# E-11_SYS_PWR.net
KiCad netlist of a schematic drawn in Altium Designer
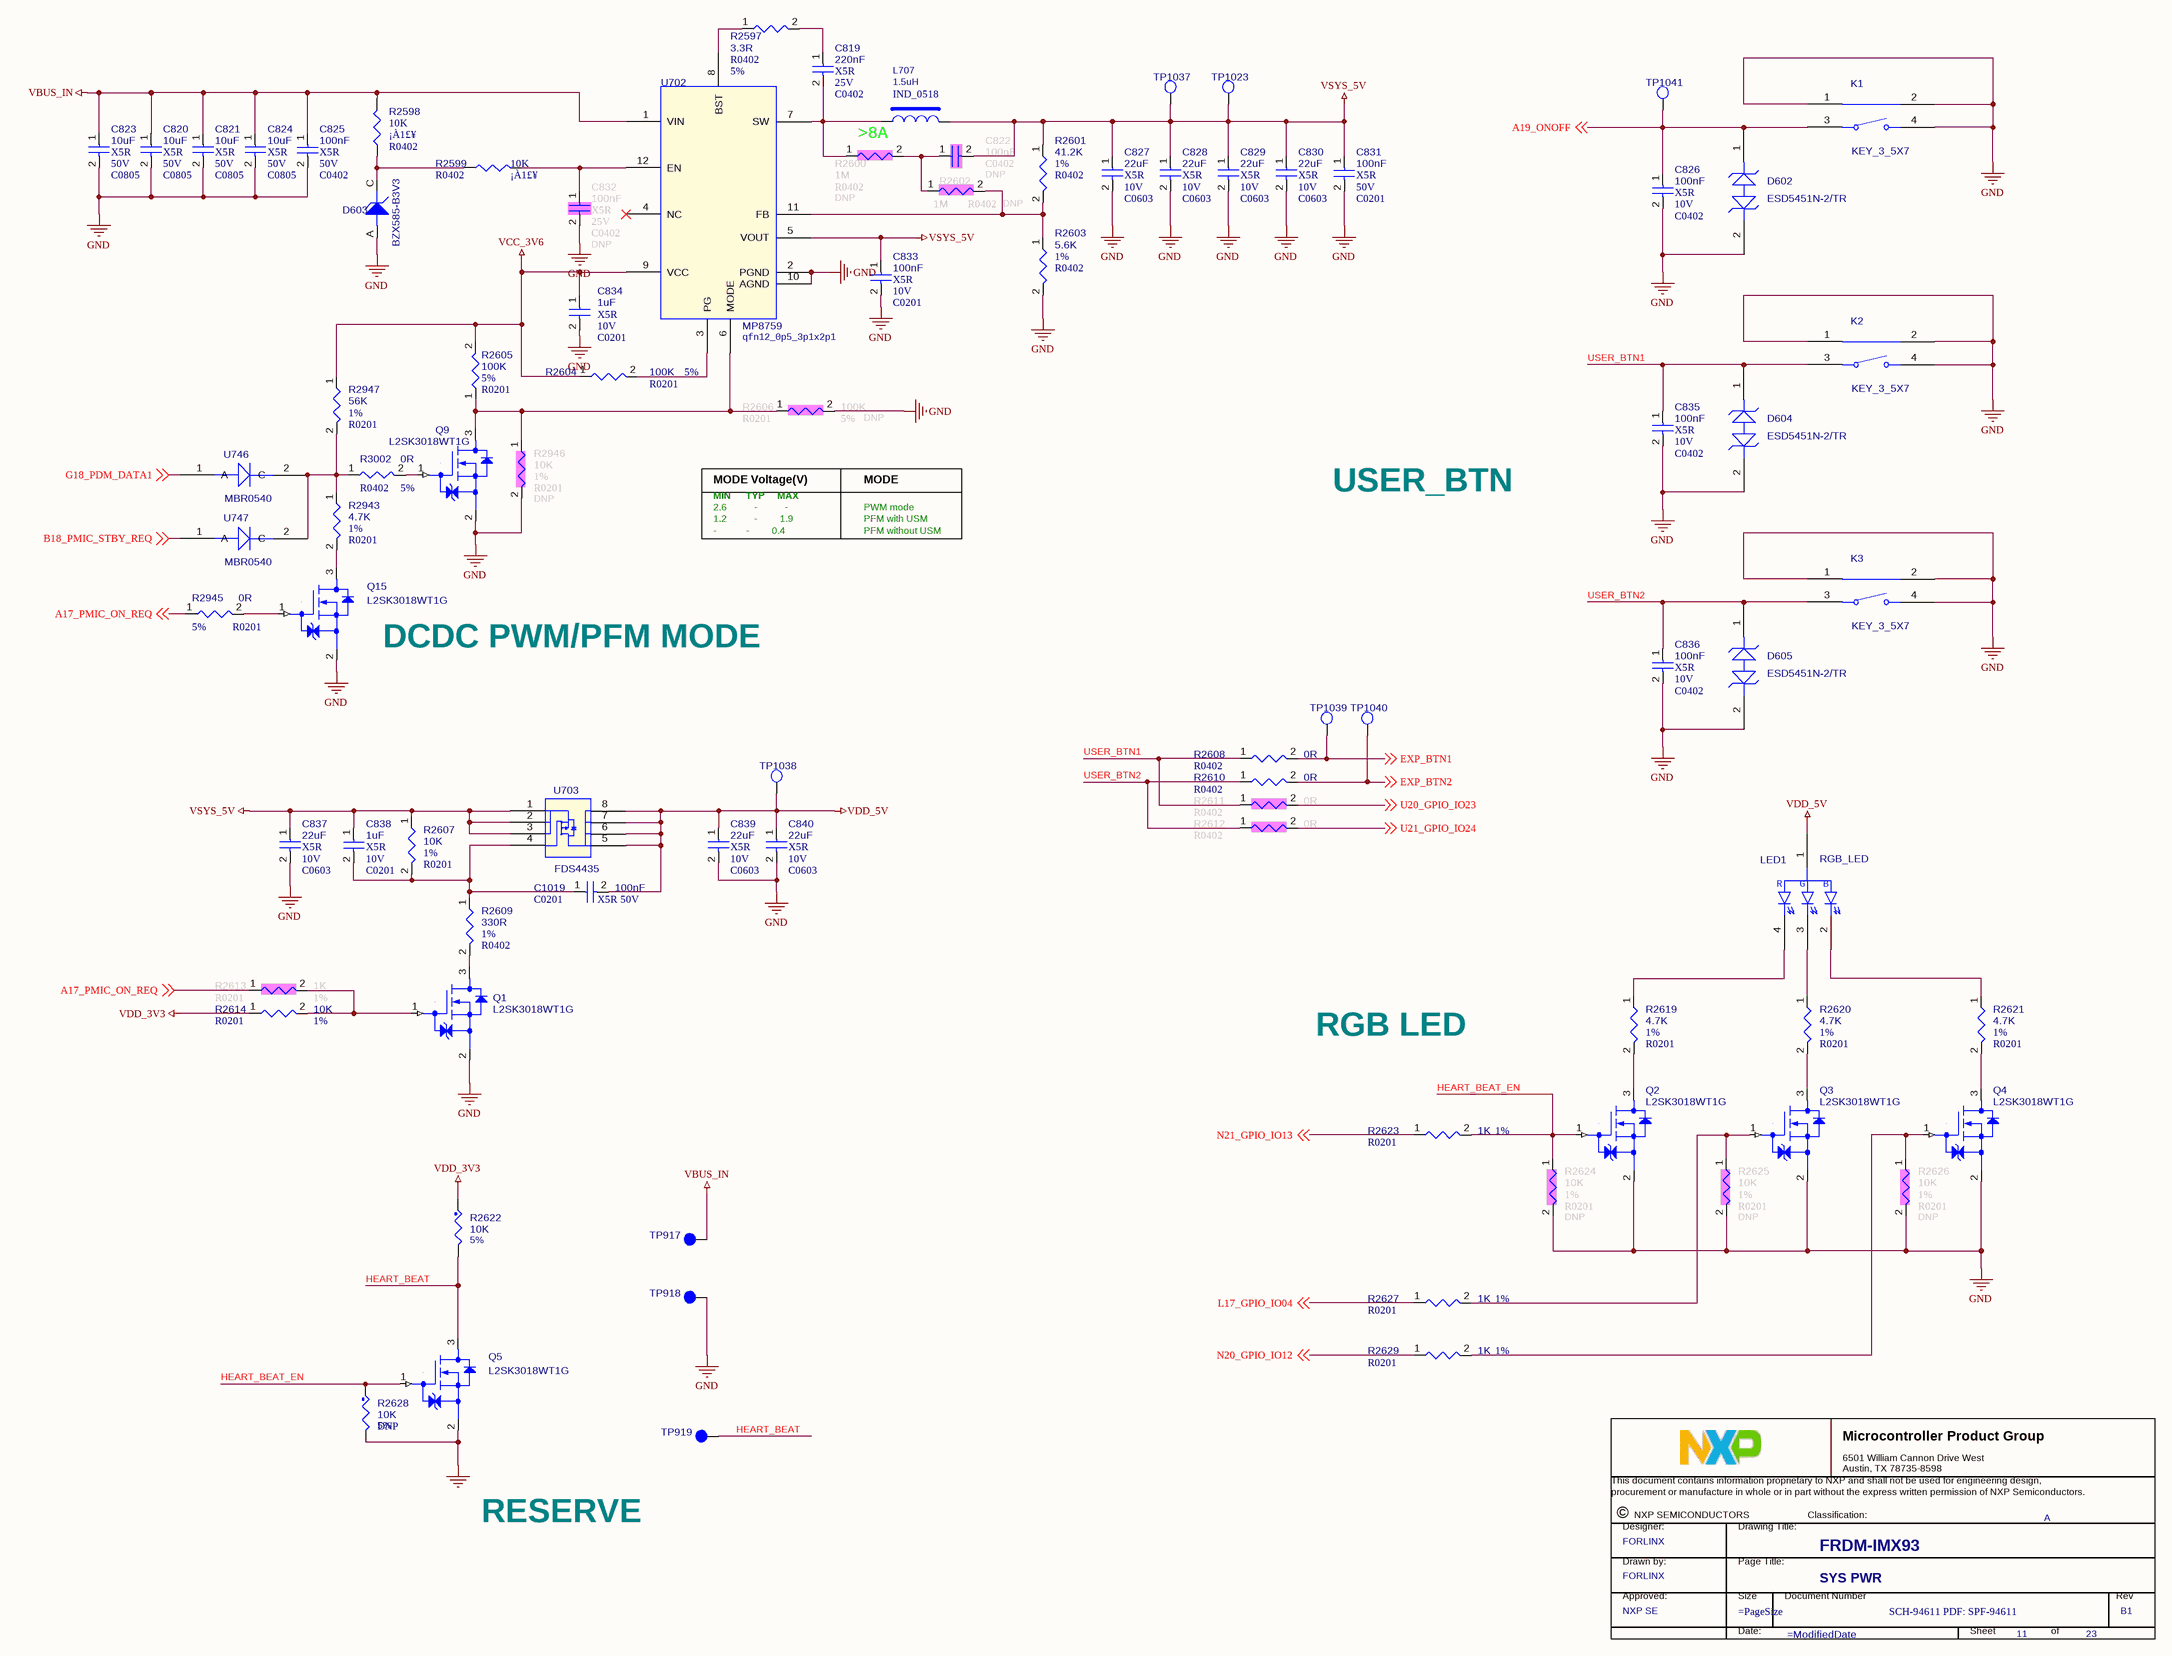
[diagram p0: E-11 SYS PWR.SchDoc]

(export (version "E")
  (design (tool "Eeschema 10.0.6"))
  (components
    (comp (ref "C819")
      (value "220nF")
      (footprint "C0402")
      (description "0402,220nF,25V,+/-10%,X5R")
      (fields
        (field (name "VOLTAGE") "25V")
        (field (name "PCB FOOTPRINT") "C0402")
        (field (name "DIELECTRIC") "X5R")
        (field (name "MANUFACTURER") "TDK")
        (field (name "TOLERANCE") "10%")
        (field (name "CREATED BY") "JJJ")
      )
      (libsource (lib "*") (part "CAP NP"))
    )
    (comp (ref "C820")
      (value "10uF")
      (footprint "C0805")
      (description "0805,10uF,50V,+/-10%,X5R")
      (fields
        (field (name "VOLTAGE") "50V")
        (field (name "PCB FOOTPRINT") "C0805")
        (field (name "DIELECTRIC") "X5R")
        (field (name "MANUFACTURER") "TDK")
        (field (name "TOLERANCE") "10%")
        (field (name "CREATED BY") "JJJ")
      )
      (libsource (lib "*") (part "CAP NP"))
    )
    (comp (ref "C821")
      (value "10uF")
      (footprint "C0805")
      (description "0805,10uF,50V,+/-10%,X5R")
      (fields
        (field (name "VOLTAGE") "50V")
        (field (name "PCB FOOTPRINT") "C0805")
        (field (name "DIELECTRIC") "X5R")
        (field (name "TOLERANCE") "10%")
        (field (name "MANUFACTURER") "TDK")
        (field (name "CREATED BY") "JJJ")
      )
      (libsource (lib "*") (part "CAP NP"))
    )
    (comp (ref "C822")
      (value "100nF")
      (footprint "C0402")
      (description "0402,100nF,50V,+/-10%,X5R")
      (fields
        (field (name "PCB FOOTPRINT") "C0402")
        (field (name "ASSY_OPT") "DNP")
        (field (name "CREATED BY") "JJJ")
      )
      (libsource (lib "*") (part "CAP NP"))
    )
    (comp (ref "C823")
      (value "10uF")
      (footprint "C0805")
      (description "0805,10uF,50V,+/-10%,X5R")
      (fields
        (field (name "VOLTAGE") "50V")
        (field (name "PCB FOOTPRINT") "C0805")
        (field (name "DIELECTRIC") "X5R")
        (field (name "MANUFACTURER") "TDK")
        (field (name "TOLERANCE") "10%")
        (field (name "CREATED BY") "JJJ")
      )
      (libsource (lib "*") (part "CAP NP"))
    )
    (comp (ref "C824")
      (value "10uF")
      (footprint "C0805")
      (description "0805,10uF,50V,+/-10%,X5R")
      (fields
        (field (name "VOLTAGE") "50V")
        (field (name "PCB FOOTPRINT") "C0805")
        (field (name "DIELECTRIC") "X5R")
        (field (name "TOLERANCE") "10%")
        (field (name "MANUFACTURER") "TDK")
        (field (name "CREATED BY") "JJJ")
      )
      (libsource (lib "*") (part "CAP NP"))
    )
    (comp (ref "C825")
      (value "100nF")
      (footprint "C0402")
      (description "0402,100nF,50V,+/-10%,X5R")
      (fields
        (field (name "VOLTAGE") "50V")
        (field (name "PCB FOOTPRINT") "C0402")
        (field (name "DIELECTRIC") "X5R")
        (field (name "TOLERANCE") "10%")
        (field (name "MANUFACTURER") "TDK")
        (field (name "CREATED BY") "JJJ")
      )
      (libsource (lib "*") (part "CAP NP"))
    )
    (comp (ref "C826")
      (value "100nF")
      (footprint "C0402")
      (description "0402,100nF,50V,+/-10%,X5R")
      (fields
        (field (name "VOLTAGE") "10V")
        (field (name "PCB FOOTPRINT") "C0402")
        (field (name "DIELECTRIC") "X5R")
        (field (name "TOLERANCE") "10%")
        (field (name "MANUFACTURER") "TDK")
        (field (name "CREATED BY") "JJJ")
      )
      (libsource (lib "*") (part "CAP NP"))
    )
    (comp (ref "C827")
      (value "22uF")
      (footprint "C0603")
      (description "0603,22uF,6.3V,+/-20%,X5R")
      (fields
        (field (name "VOLTAGE") "10V")
        (field (name "PCB FOOTPRINT") "C0603")
        (field (name "DIELECTRIC") "X5R")
        (field (name "MANUFACTURER") "TDK")
        (field (name "TOLERANCE") "10%")
        (field (name "CREATED BY") "JJJ")
      )
      (libsource (lib "*") (part "CAP NP"))
    )
    (comp (ref "C828")
      (value "22uF")
      (footprint "C0603")
      (description "0603,22uF,6.3V,+/-20%,X5R")
      (fields
        (field (name "VOLTAGE") "10V")
        (field (name "PCB FOOTPRINT") "C0603")
        (field (name "DIELECTRIC") "X5R")
        (field (name "MANUFACTURER") "TDK")
        (field (name "TOLERANCE") "10%")
        (field (name "CREATED BY") "JJJ")
      )
      (libsource (lib "*") (part "CAP NP"))
    )
    (comp (ref "C829")
      (value "22uF")
      (footprint "C0603")
      (description "0603,22uF,6.3V,+/-20%,X5R")
      (fields
        (field (name "VOLTAGE") "10V")
        (field (name "PCB FOOTPRINT") "C0603")
        (field (name "DIELECTRIC") "X5R")
        (field (name "TOLERANCE") "10%")
        (field (name "MANUFACTURER") "TDK")
        (field (name "CREATED BY") "JJJ")
      )
      (libsource (lib "*") (part "CAP NP"))
    )
    (comp (ref "C830")
      (value "22uF")
      (footprint "C0603")
      (description "0603,22uF,6.3V,+/-20%,X5R")
      (fields
        (field (name "VOLTAGE") "10V")
        (field (name "PCB FOOTPRINT") "C0603")
        (field (name "DIELECTRIC") "X5R")
        (field (name "TOLERANCE") "10%")
        (field (name "MANUFACTURER") "TDK")
        (field (name "CREATED BY") "JJJ")
      )
      (libsource (lib "*") (part "CAP NP"))
    )
    (comp (ref "C831")
      (value "100nF")
      (footprint "C0201")
      (description "0201,100nF,25V,+/-10%,X5R")
      (fields
        (field (name "VOLTAGE") "50V")
        (field (name "PCB FOOTPRINT") "C0201")
        (field (name "DIELECTRIC") "X5R")
        (field (name "TOLERANCE") "10%")
        (field (name "MANUFACTURER") "TDK")
        (field (name "CREATED BY") "JJJ")
      )
      (libsource (lib "*") (part "CAP NP"))
    )
    (comp (ref "C832")
      (value "100nF")
      (footprint "C0402")
      (description "0402,100nF,50V,+/-10%,X5R")
      (fields
        (field (name "VOLTAGE") "25V")
        (field (name "PCB FOOTPRINT") "C0402")
        (field (name "DIELECTRIC") "X5R")
        (field (name "ASSY_OPT") "DNP")
        (field (name "MANUFACTURER") "TDK")
        (field (name "TOLERANCE") "10%")
        (field (name "CREATED BY") "JJJ")
      )
      (libsource (lib "*") (part "CAP NP"))
    )
    (comp (ref "C833")
      (value "100nF")
      (footprint "C0201")
      (description "0201,100nF,25V,+/-10%,X5R")
      (fields
        (field (name "VOLTAGE") "10V")
        (field (name "PCB FOOTPRINT") "C0201")
        (field (name "DIELECTRIC") "X5R")
        (field (name "TOLERANCE") "10%")
        (field (name "MANUFACTURER") "TDK")
        (field (name "CREATED BY") "JJJ")
      )
      (libsource (lib "*") (part "CAP NP"))
    )
    (comp (ref "C834")
      (value "1uF")
      (footprint "C0201")
      (description "0201,1uF,10V,+/-20%,X5R")
      (fields
        (field (name "VOLTAGE") "10V")
        (field (name "PCB FOOTPRINT") "C0201")
        (field (name "DIELECTRIC") "X5R")
        (field (name "MANUFACTURER") "TDK")
        (field (name "TOLERANCE") "10%")
        (field (name "CREATED BY") "JJJ")
      )
      (libsource (lib "*") (part "CAP NP"))
    )
    (comp (ref "C835")
      (value "100nF")
      (footprint "C0402")
      (description "0402,100nF,50V,+/-10%,X5R")
      (fields
        (field (name "VOLTAGE") "10V")
        (field (name "PCB FOOTPRINT") "C0402")
        (field (name "DIELECTRIC") "X5R")
        (field (name "MANUFACTURER") "TDK")
        (field (name "TOLERANCE") "10%")
        (field (name "CREATED BY") "JJJ")
      )
      (libsource (lib "*") (part "CAP NP"))
    )
    (comp (ref "C836")
      (value "100nF")
      (footprint "C0402")
      (description "0402,100nF,50V,+/-10%,X5R")
      (fields
        (field (name "VOLTAGE") "10V")
        (field (name "PCB FOOTPRINT") "C0402")
        (field (name "DIELECTRIC") "X5R")
        (field (name "MANUFACTURER") "TDK")
        (field (name "TOLERANCE") "10%")
        (field (name "CREATED BY") "JJJ")
      )
      (libsource (lib "*") (part "CAP NP"))
    )
    (comp (ref "C837")
      (value "22uF")
      (footprint "C0603")
      (description "0603,22uF,6.3V,+/-20%,X5R")
      (fields
        (field (name "VOLTAGE") "10V")
        (field (name "PCB FOOTPRINT") "C0603")
        (field (name "DIELECTRIC") "X5R")
        (field (name "TOLERANCE") "10%")
        (field (name "MANUFACTURER") "TDK")
        (field (name "CREATED BY") "JJJ")
      )
      (libsource (lib "*") (part "CAP NP"))
    )
    (comp (ref "C838")
      (value "1uF")
      (footprint "C0201")
      (description "0201,1uF,10V,+/-20%,X5R")
      (fields
        (field (name "VOLTAGE") "10V")
        (field (name "PCB FOOTPRINT") "C0201")
        (field (name "DIELECTRIC") "X5R")
        (field (name "MANUFACTURER") "TDK")
        (field (name "TOLERANCE") "10%")
        (field (name "CREATED BY") "JJJ")
      )
      (libsource (lib "*") (part "CAP NP"))
    )
    (comp (ref "C839")
      (value "22uF")
      (footprint "C0603")
      (description "0603,22uF,6.3V,+/-20%,X5R")
      (fields
        (field (name "VOLTAGE") "10V")
        (field (name "PCB FOOTPRINT") "C0603")
        (field (name "DIELECTRIC") "X5R")
        (field (name "MANUFACTURER") "TDK")
        (field (name "TOLERANCE") "10%")
        (field (name "CREATED BY") "JJJ")
      )
      (libsource (lib "*") (part "CAP NP"))
    )
    (comp (ref "C840")
      (value "22uF")
      (footprint "C0603")
      (description "0603,22uF,6.3V,+/-20%,X5R")
      (fields
        (field (name "VOLTAGE") "10V")
        (field (name "PCB FOOTPRINT") "C0603")
        (field (name "DIELECTRIC") "X5R")
        (field (name "TOLERANCE") "10%")
        (field (name "MANUFACTURER") "TDK")
        (field (name "CREATED BY") "JJJ")
      )
      (libsource (lib "*") (part "CAP NP"))
    )
    (comp (ref "C1019")
      (value "100nF")
      (footprint "C0201")
      (description "0201,100nF,25V,+/-10%,X5R")
      (fields
        (field (name "VOLTAGE") "50V")
        (field (name "PCB FOOTPRINT") "C0201")
        (field (name "DIELECTRIC") "X5R")
        (field (name "TOLERANCE") "10%")
        (field (name "MANUFACTURER") "TDK")
        (field (name "CREATED BY") "JJJ")
      )
      (libsource (lib "*") (part "CAP NP"))
    )
    (comp (ref "D602")
      (value "ESD5451N-2/TR")
      (footprint "0402TVS")
      (libsource (lib "*") (part "ESD5451N-2/TR"))
    )
    (comp (ref "D603")
      (value "BZX585-B3V3")
      (footprint "sod523")
      (description "BZX585-B3V3,3.3V,SOD523")
      (libsource (lib "*") (part "ZDIODE"))
    )
    (comp (ref "D604")
      (value "ESD5451N-2/TR")
      (footprint "0402TVS")
      (libsource (lib "*") (part "ESD5451N-2/TR"))
    )
    (comp (ref "D605")
      (value "ESD5451N-2/TR")
      (footprint "0402TVS")
      (libsource (lib "*") (part "ESD5451N-2/TR"))
    )
    (comp (ref "K1")
      (value "KEY_3_5X7")
      (footprint "KEY_3_5X7")
      (description "3x6mm,KEY")
      (libsource (lib "*") (part "1188E_1K"))
    )
    (comp (ref "K2")
      (value "KEY_3_5X7")
      (footprint "KEY_3_5X7")
      (description "3x6mm,KEY")
      (libsource (lib "*") (part "1188E_1K"))
    )
    (comp (ref "K3")
      (value "KEY_3_5X7")
      (footprint "KEY_3_5X7")
      (description "3x6mm,KEY")
      (libsource (lib "*") (part "1188E_1K"))
    )
    (comp (ref "L707")
      (value "1.5uH")
      (footprint "IND_0518")
      (description "1.5uH+/-20%,5.2*5.4*1.6,7.5A/8A")
      (fields
        (field (name "PCB FOOTPRINT") "IND_0518")
        (field (name "TOLERANCE") "20%")
        (field (name "MANUFACTURER") "Vishay")
        (field (name "OPTION") ">8A")
        (field (name "CREATED BY") "JJJ")
      )
      (libsource (lib "*") (part "INDUCTORS OF FERRITE"))
    )
    (comp (ref "LED1") (value "RGB_LED") (footprint "smd_rgb_1_5x3") (libsource (lib "*") (part "RGB_LED")))
    (comp (ref "Q1")
      (value "L2SK3018WT1G")
      (footprint "sc70_3")
      (libsource (lib "*") (part "NX3008NBKW_SOT323"))
    )
    (comp (ref "Q2")
      (value "L2SK3018WT1G")
      (footprint "sc70_3")
      (libsource (lib "*") (part "NX3008NBKW_SOT323"))
    )
    (comp (ref "Q3")
      (value "L2SK3018WT1G")
      (footprint "sc70_3")
      (libsource (lib "*") (part "NX3008NBKW_SOT323"))
    )
    (comp (ref "Q4")
      (value "L2SK3018WT1G")
      (footprint "sc70_3")
      (libsource (lib "*") (part "NX3008NBKW_SOT323"))
    )
    (comp (ref "Q5")
      (value "L2SK3018WT1G")
      (footprint "sc70_3")
      (libsource (lib "*") (part "NX3008NBKW_SOT323"))
    )
    (comp (ref "Q9")
      (value "L2SK3018WT1G")
      (footprint "sc70_3")
      (libsource (lib "*") (part "NX3008NBKW_SOT323"))
    )
    (comp (ref "Q15")
      (value "L2SK3018WT1G")
      (footprint "sc70_3")
      (libsource (lib "*") (part "NX3008NBKW_SOT323"))
    )
    (comp (ref "R2597")
      (value "3.3R")
      (footprint "R0402")
      (description "0402,3.3Ohm,+/-1%")
      (fields
        (field (name "PCB FOOTPRINT") "R0402")
        (field (name "TOLERANCE") "5%")
        (field (name "MANUFACTURER") "YAGEO")
        (field (name "CREATED BY") "YTL")
      )
      (libsource (lib "*") (part "RESISTOR"))
    )
    (comp (ref "R2598")
      (value "10K")
      (footprint "R0402")
      (description "0402,10K,+/-1%")
      (fields (field (name "PCB FOOTPRINT") "R0402") (field (name "PRECISION") "±1％"))
      (libsource (lib "*") (part "R0402,4.7K"))
    )
    (comp (ref "R2599")
      (value "10K")
      (footprint "R0402")
      (description "0402,10K,+/-1%")
      (fields (field (name "PCB FOOTPRINT") "R0402") (field (name "PRECISION") "±1％"))
      (libsource (lib "*") (part "R0402,4.7K"))
    )
    (comp (ref "R2600")
      (value "1M")
      (footprint "R0402")
      (description "0402,1M,+/-1%")
      (fields
        (field (name "PCB FOOTPRINT") "R0402")
        (field (name "ASSY_OPT") "DNP")
        (field (name "CREATED BY") "JJJ")
      )
      (libsource (lib "*") (part "RESISTOR"))
    )
    (comp (ref "R2601")
      (value "41.2K")
      (footprint "R0402")
      (description "0402,41.2K,+/-1%")
      (fields
        (field (name "PCB FOOTPRINT") "R0402")
        (field (name "TOLERANCE") "1%")
        (field (name "MANUFACTURER") "YAGEO")
        (field (name "CREATED BY") "YTL")
      )
      (libsource (lib "*") (part "RESISTOR"))
    )
    (comp (ref "R2602")
      (value "1M")
      (footprint "R0402")
      (description "0402,1M,+/-1%")
      (fields
        (field (name "PCB FOOTPRINT") "R0402")
        (field (name "ASSY_OPT") "DNP")
        (field (name "CREATED BY") "JJJ")
      )
      (libsource (lib "*") (part "RESISTOR"))
    )
    (comp (ref "R2603")
      (value "5.6K")
      (footprint "R0402")
      (description "0402,5.6K,+/-1%")
      (fields
        (field (name "PCB FOOTPRINT") "R0402")
        (field (name "TOLERANCE") "1%")
        (field (name "MANUFACTURER") "YAGEO")
        (field (name "CREATED BY") "YTL")
      )
      (libsource (lib "*") (part "RESISTOR"))
    )
    (comp (ref "R2604")
      (value "100K")
      (footprint "R0201")
      (description "0201,100K,+/-1%")
      (fields
        (field (name "PCB FOOTPRINT") "R0201")
        (field (name "TOLERANCE") "5%")
        (field (name "MANUFACTURER") "YAGEO")
        (field (name "CREATED BY") "YTL")
      )
      (libsource (lib "*") (part "RESISTOR"))
    )
    (comp (ref "R2605")
      (value "100K")
      (footprint "R0201")
      (description "0201,100K,+/-1%")
      (fields
        (field (name "PCB FOOTPRINT") "R0201")
        (field (name "TOLERANCE") "5%")
        (field (name "MANUFACTURER") "YAGEO")
        (field (name "CREATED BY") "YTL")
      )
      (libsource (lib "*") (part "RESISTOR"))
    )
    (comp (ref "R2606")
      (value "100K")
      (footprint "R0201")
      (description "0201,100K,+/-1%")
      (fields
        (field (name "PCB FOOTPRINT") "R0201")
        (field (name "TOLERANCE") "5%")
        (field (name "ASSY_OPT") "DNP")
        (field (name "MANUFACTURER") "YAGEO")
        (field (name "CREATED BY") "YTL")
      )
      (libsource (lib "*") (part "RESISTOR"))
    )
    (comp (ref "R2607")
      (value "10K")
      (footprint "R0201")
      (description "0201,10K,+/-5%")
      (fields
        (field (name "PCB FOOTPRINT") "R0201")
        (field (name "TOLERANCE") "1%")
        (field (name "MANUFACTURER") "YAGEO")
        (field (name "CREATED BY") "YTL")
      )
      (libsource (lib "*") (part "RESISTOR"))
    )
    (comp (ref "R2608")
      (value "0R")
      (footprint "R0402")
      (description "0402,0Ohm,+/-1%")
      (fields
        (field (name "PCB FOOTPRINT") "R0402")
        (field (name "TOLERANCE") "1%")
        (field (name "MANUFACTURER") "YAGEO")
        (field (name "CREATED BY") "YTL")
      )
      (libsource (lib "*") (part "RESISTOR"))
    )
    (comp (ref "R2609")
      (value "330R")
      (footprint "R0402")
      (description "0402,330Ohm,+/-1%")
      (fields
        (field (name "PCB FOOTPRINT") "R0402")
        (field (name "TOLERANCE") "1%")
        (field (name "MANUFACTURER") "YAGEO")
        (field (name "CREATED BY") "YTL")
      )
      (libsource (lib "*") (part "RESISTOR"))
    )
    (comp (ref "R2610")
      (value "0R")
      (footprint "R0402")
      (description "0402,0Ohm,+/-1%")
      (fields
        (field (name "PCB FOOTPRINT") "R0402")
        (field (name "TOLERANCE") "1%")
        (field (name "MANUFACTURER") "YAGEO")
        (field (name "CREATED BY") "YTL")
      )
      (libsource (lib "*") (part "RESISTOR"))
    )
    (comp (ref "R2611")
      (value "0R")
      (footprint "R0402")
      (description "0402,0Ohm,+/-1%")
      (fields
        (field (name "PCB FOOTPRINT") "R0402")
        (field (name "TOLERANCE") "1%")
        (field (name "MANUFACTURER") "YAGEO")
        (field (name "CREATED BY") "YTL")
      )
      (libsource (lib "*") (part "RESISTOR"))
    )
    (comp (ref "R2612")
      (value "0R")
      (footprint "R0402")
      (description "0402,0Ohm,+/-1%")
      (fields
        (field (name "PCB FOOTPRINT") "R0402")
        (field (name "TOLERANCE") "1%")
        (field (name "MANUFACTURER") "YAGEO")
        (field (name "CREATED BY") "YTL")
      )
      (libsource (lib "*") (part "RESISTOR"))
    )
    (comp (ref "R2613")
      (value "1K")
      (footprint "R0201")
      (description "0201,1K,+/-1%")
      (fields
        (field (name "PCB FOOTPRINT") "R0201")
        (field (name "TOLERANCE") "1%")
        (field (name "MANUFACTURER") "YAGEO")
        (field (name "CREATED BY") "YTL")
      )
      (libsource (lib "*") (part "RESISTOR"))
    )
    (comp (ref "R2614")
      (value "10K")
      (footprint "R0201")
      (description "0201,10K,+/-5%")
      (fields
        (field (name "PCB FOOTPRINT") "R0201")
        (field (name "TOLERANCE") "1%")
        (field (name "MANUFACTURER") "YAGEO")
        (field (name "CREATED BY") "YTL")
      )
      (libsource (lib "*") (part "RESISTOR"))
    )
    (comp (ref "R2619")
      (value "4.7K")
      (footprint "R0201")
      (description "0201,4.7K,+/-1%")
      (fields
        (field (name "PCB FOOTPRINT") "R0201")
        (field (name "TOLERANCE") "1%")
        (field (name "MANUFACTURER") "YAGEO")
        (field (name "CREATED BY") "YTL")
      )
      (libsource (lib "*") (part "RESISTOR"))
    )
    (comp (ref "R2620")
      (value "4.7K")
      (footprint "R0201")
      (description "0201,4.7K,+/-1%")
      (fields
        (field (name "PCB FOOTPRINT") "R0201")
        (field (name "TOLERANCE") "1%")
        (field (name "MANUFACTURER") "YAGEO")
        (field (name "CREATED BY") "YTL")
      )
      (libsource (lib "*") (part "RESISTOR"))
    )
    (comp (ref "R2621")
      (value "4.7K")
      (footprint "R0201")
      (description "0201,4.7K,+/-1%")
      (fields
        (field (name "PCB FOOTPRINT") "R0201")
        (field (name "TOLERANCE") "1%")
        (field (name "MANUFACTURER") "YAGEO")
        (field (name "CREATED BY") "YTL")
      )
      (libsource (lib "*") (part "RESISTOR"))
    )
    (comp (ref "R2622")
      (value "10K")
      (footprint "R0201")
      (description "0201,10K,+/-5%")
      (fields (field (name "TOLERANCE") "5%"))
      (libsource (lib "*") (part "RES"))
    )
    (comp (ref "R2623")
      (value "1K")
      (footprint "R0201")
      (description "0201,1K,+/-1%")
      (fields
        (field (name "PCB FOOTPRINT") "R0201")
        (field (name "TOLERANCE") "1%")
        (field (name "MANUFACTURER") "YAGEO")
        (field (name "CREATED BY") "YTL")
      )
      (libsource (lib "*") (part "RESISTOR"))
    )
    (comp (ref "R2624")
      (value "10K")
      (footprint "R0201")
      (description "0201,10K,+/-5%")
      (fields
        (field (name "PCB FOOTPRINT") "R0201")
        (field (name "TOLERANCE") "1%")
        (field (name "ASSY_OPT") "DNP")
        (field (name "MANUFACTURER") "YAGEO")
        (field (name "CREATED BY") "YTL")
      )
      (libsource (lib "*") (part "RESISTOR"))
    )
    (comp (ref "R2625")
      (value "10K")
      (footprint "R0201")
      (description "0201,10K,+/-5%")
      (fields
        (field (name "PCB FOOTPRINT") "R0201")
        (field (name "TOLERANCE") "1%")
        (field (name "MANUFACTURER") "YAGEO")
        (field (name "ASSY_OPT") "DNP")
        (field (name "CREATED BY") "YTL")
      )
      (libsource (lib "*") (part "RESISTOR"))
    )
    (comp (ref "R2626")
      (value "10K")
      (footprint "R0201")
      (description "0201,10K,+/-5%")
      (fields
        (field (name "PCB FOOTPRINT") "R0201")
        (field (name "TOLERANCE") "1%")
        (field (name "MANUFACTURER") "YAGEO")
        (field (name "ASSY_OPT") "DNP")
        (field (name "CREATED BY") "YTL")
      )
      (libsource (lib "*") (part "RESISTOR"))
    )
    (comp (ref "R2627")
      (value "1K")
      (footprint "R0201")
      (description "0201,1K,+/-1%")
      (fields
        (field (name "PCB FOOTPRINT") "R0201")
        (field (name "TOLERANCE") "1%")
        (field (name "MANUFACTURER") "YAGEO")
        (field (name "CREATED BY") "YTL")
      )
      (libsource (lib "*") (part "RESISTOR"))
    )
    (comp (ref "R2628")
      (value "10K")
      (footprint "R0201")
      (description "0201,10K,+/-5%")
      (fields (field (name "ASSY_OPT") "DNP") (field (name "TOLERANCE") "5%"))
      (libsource (lib "*") (part "RES"))
    )
    (comp (ref "R2629")
      (value "1K")
      (footprint "R0201")
      (description "0201,1K,+/-1%")
      (fields
        (field (name "PCB FOOTPRINT") "R0201")
        (field (name "TOLERANCE") "1%")
        (field (name "MANUFACTURER") "YAGEO")
        (field (name "CREATED BY") "YTL")
      )
      (libsource (lib "*") (part "RESISTOR"))
    )
    (comp (ref "R2943")
      (value "4.7K")
      (footprint "R0201")
      (description "0201,4.7K,+/-1%")
      (fields
        (field (name "PCB FOOTPRINT") "R0201")
        (field (name "TOLERANCE") "1%")
        (field (name "MANUFACTURER") "YAGEO")
        (field (name "CREATED BY") "YTL")
      )
      (libsource (lib "*") (part "RESISTOR"))
    )
    (comp (ref "R2945")
      (value "0R")
      (footprint "R0201")
      (description "0201,0Ohm,+/-5%")
      (fields
        (field (name "PCB FOOTPRINT") "R0201")
        (field (name "TOLERANCE") "5%")
        (field (name "MANUFACTURER") "YAGEO")
        (field (name "CREATED BY") "YTL")
      )
      (libsource (lib "*") (part "RESISTOR"))
    )
    (comp (ref "R2946")
      (value "10K")
      (footprint "R0201")
      (description "0201,10K,+/-5%")
      (fields
        (field (name "PCB FOOTPRINT") "R0201")
        (field (name "TOLERANCE") "1%")
        (field (name "ASSY_OPT") "DNP")
        (field (name "MANUFACTURER") "YAGEO")
        (field (name "CREATED BY") "YTL")
      )
      (libsource (lib "*") (part "RESISTOR"))
    )
    (comp (ref "R2947")
      (value "56K")
      (footprint "R0201")
      (description "0201,56K,+/-1%")
      (fields
        (field (name "PCB FOOTPRINT") "R0201")
        (field (name "TOLERANCE") "1%")
        (field (name "MANUFACTURER") "YAGEO")
        (field (name "CREATED BY") "YTL")
      )
      (libsource (lib "*") (part "RESISTOR"))
    )
    (comp (ref "R3002")
      (value "0R")
      (footprint "R0402")
      (description "0402,0Ohm,+/-1%")
      (fields
        (field (name "PCB FOOTPRINT") "R0402")
        (field (name "TOLERANCE") "5%")
        (field (name "MANUFACTURER") "YAGEO")
        (field (name "CREATED BY") "YTL")
      )
      (libsource (lib "*") (part "RESISTOR"))
    )
    (comp (ref "TP917")
      (value "TPAD_1212")
      (footprint "tpad_1212")
      (description "no part to order")
      (libsource (lib "*") (part "TESTLOOP"))
    )
    (comp (ref "TP918")
      (value "TPAD_1212")
      (footprint "tpad_1212")
      (description "no part to order")
      (libsource (lib "*") (part "TESTLOOP"))
    )
    (comp (ref "TP919")
      (value "TPAD_1212")
      (footprint "tpad_1212")
      (description "no part to order")
      (libsource (lib "*") (part "TESTLOOP"))
    )
    (comp (ref "TP1023")
      (value "TPAD_020")
      (footprint "tpad_020")
      (description "no part to order")
      (libsource (lib "*") (part "T POINT R"))
    )
    (comp (ref "TP1037")
      (value "TPAD_020")
      (footprint "tpad_020")
      (description "no part to order")
      (libsource (lib "*") (part "T POINT R"))
    )
    (comp (ref "TP1038")
      (value "TPAD_020")
      (footprint "tpad_020")
      (description "no part to order")
      (libsource (lib "*") (part "T POINT R"))
    )
    (comp (ref "TP1039")
      (value "TPAD_020")
      (footprint "tpad_020")
      (description "no part to order")
      (libsource (lib "*") (part "T POINT R"))
    )
    (comp (ref "TP1040")
      (value "TPAD_020")
      (footprint "tpad_020")
      (description "no part to order")
      (libsource (lib "*") (part "T POINT R"))
    )
    (comp (ref "TP1041")
      (value "TPAD_020")
      (footprint "tpad_020")
      (description "no part to order")
      (libsource (lib "*") (part "T POINT R"))
    )
    (comp (ref "U702")
      (value "MP8759")
      (footprint "qfn12_0p5_3p1x2p1")
      (fields (field (name "PCB FOOTPRINT") "qfn12_0p5_3p1x2p1"))
      (libsource (lib "*") (part "MP8759_6"))
    )
    (comp (ref "U703")
      (value "FDS4435")
      (footprint "SOP8_1_27")
      (description "FDS4435BZ,SO-8,PMOS")
      (libsource (lib "*") (part "FDS4435"))
    )
    (comp (ref "U746")
      (value "MBR0540")
      (footprint "SOD_123")
      (description "MBR0540,SOD123")
      (libsource (lib "*") (part "MBR0540_1"))
    )
    (comp (ref "U747")
      (value "MBR0540")
      (footprint "SOD_123")
      (description "MBR0540,SOD123")
      (libsource (lib "*") (part "MBR0540_2"))
    )
  )
  (nets
    (net (code "1") (name "/HEART_BEAT") (class "Default")
      (node (ref "Q5") (pin "3") (pinfunction "DRAIN_3") (pintype "passive"))
      (node (ref "R2622") (pin "2") (pinfunction "2_2") (pintype "passive"))
      (node (ref "TP919") (pin "1") (pinfunction "Pin1_1") (pintype "passive"))
    )
    (net (code "2") (name "/HEART_BEAT_EN") (class "Default")
      (node (ref "Q2") (pin "1") (pinfunction "GATE_1") (pintype "input"))
      (node (ref "Q5") (pin "1") (pinfunction "GATE_1") (pintype "input"))
      (node (ref "R2623") (pin "2") (pinfunction "2_2") (pintype "passive"))
      (node (ref "R2624") (pin "1") (pinfunction "1_1") (pintype "passive"))
      (node (ref "R2628") (pin "1") (pinfunction "1_1") (pintype "passive"))
    )
    (net (code "3") (name "/USER_BTN1") (class "Default")
      (node (ref "C835") (pin "1") (pinfunction "1_1") (pintype "passive"))
      (node (ref "D604") (pin "1") (pinfunction "1_1") (pintype "passive"))
      (node (ref "K2") (pin "3") (pinfunction "3_3") (pintype "passive"))
      (node (ref "R2608") (pin "1") (pinfunction "1_1") (pintype "passive"))
      (node (ref "R2611") (pin "1") (pinfunction "1_1") (pintype "passive"))
    )
    (net (code "4") (name "/USER_BTN2") (class "Default")
      (node (ref "C836") (pin "1") (pinfunction "1_1") (pintype "passive"))
      (node (ref "D605") (pin "1") (pinfunction "1_1") (pintype "passive"))
      (node (ref "K3") (pin "3") (pinfunction "3_3") (pintype "passive"))
      (node (ref "R2610") (pin "1") (pinfunction "1_1") (pintype "passive"))
      (node (ref "R2612") (pin "1") (pinfunction "1_1") (pintype "passive"))
    )
    (net (code "5") (name "A17_PMIC_ON_REQ") (class "Default")
      (node (ref "R2613") (pin "1") (pinfunction "1_1") (pintype "passive"))
      (node (ref "R2945") (pin "1") (pinfunction "1_1") (pintype "passive"))
    )
    (net (code "6") (name "A19_ONOFF") (class "Default")
      (node (ref "C826") (pin "1") (pinfunction "1_1") (pintype "passive"))
      (node (ref "D602") (pin "1") (pinfunction "1_1") (pintype "passive"))
      (node (ref "K1") (pin "3") (pinfunction "3_3") (pintype "passive"))
      (node (ref "TP1041") (pin "1") (pinfunction "TP_1") (pintype "passive"))
    )
    (net (code "7") (name "B18_PMIC_STBY_REQ") (class "Default")
      (node (ref "U747") (pin "1") (pinfunction "A_1") (pintype "passive"))
    )
    (net (code "8") (name "EXP_BTN1") (class "Default")
      (node (ref "R2608") (pin "2") (pinfunction "2_2") (pintype "passive"))
      (node (ref "TP1039") (pin "1") (pinfunction "TP_1") (pintype "passive"))
    )
    (net (code "9") (name "EXP_BTN2") (class "Default")
      (node (ref "R2610") (pin "2") (pinfunction "2_2") (pintype "passive"))
      (node (ref "TP1040") (pin "1") (pinfunction "TP_1") (pintype "passive"))
    )
    (net (code "10") (name "G18_PDM_DATA1") (class "Default")
      (node (ref "U746") (pin "1") (pinfunction "A_1") (pintype "passive"))
    )
    (net (code "11") (name "GND") (class "Default")
      (node (ref "C820") (pin "2") (pinfunction "2_2") (pintype "passive"))
      (node (ref "C821") (pin "2") (pinfunction "2_2") (pintype "passive"))
      (node (ref "C823") (pin "2") (pinfunction "2_2") (pintype "passive"))
      (node (ref "C824") (pin "2") (pinfunction "2_2") (pintype "passive"))
      (node (ref "C825") (pin "2") (pinfunction "2_2") (pintype "passive"))
      (node (ref "C826") (pin "2") (pinfunction "2_2") (pintype "passive"))
      (node (ref "C827") (pin "2") (pinfunction "2_2") (pintype "passive"))
      (node (ref "C828") (pin "2") (pinfunction "2_2") (pintype "passive"))
      (node (ref "C829") (pin "2") (pinfunction "2_2") (pintype "passive"))
      (node (ref "C830") (pin "2") (pinfunction "2_2") (pintype "passive"))
      (node (ref "C831") (pin "2") (pinfunction "2_2") (pintype "passive"))
      (node (ref "C832") (pin "2") (pinfunction "2_2") (pintype "passive"))
      (node (ref "C833") (pin "2") (pinfunction "2_2") (pintype "passive"))
      (node (ref "C834") (pin "2") (pinfunction "2_2") (pintype "passive"))
      (node (ref "C835") (pin "2") (pinfunction "2_2") (pintype "passive"))
      (node (ref "C836") (pin "2") (pinfunction "2_2") (pintype "passive"))
      (node (ref "C837") (pin "2") (pinfunction "2_2") (pintype "passive"))
      (node (ref "C839") (pin "2") (pinfunction "2_2") (pintype "passive"))
      (node (ref "C840") (pin "2") (pinfunction "2_2") (pintype "passive"))
      (node (ref "D602") (pin "2") (pinfunction "2_2") (pintype "passive"))
      (node (ref "D603") (pin "A") (pinfunction "ANODE_A") (pintype "passive"))
      (node (ref "D604") (pin "2") (pinfunction "2_2") (pintype "passive"))
      (node (ref "D605") (pin "2") (pinfunction "2_2") (pintype "passive"))
      (node (ref "K1") (pin "1") (pinfunction "1_1") (pintype "passive"))
      (node (ref "K1") (pin "2") (pinfunction "2_2") (pintype "passive"))
      (node (ref "K1") (pin "4") (pinfunction "4_4") (pintype "passive"))
      (node (ref "K2") (pin "1") (pinfunction "1_1") (pintype "passive"))
      (node (ref "K2") (pin "2") (pinfunction "2_2") (pintype "passive"))
      (node (ref "K2") (pin "4") (pinfunction "4_4") (pintype "passive"))
      (node (ref "K3") (pin "1") (pinfunction "1_1") (pintype "passive"))
      (node (ref "K3") (pin "2") (pinfunction "2_2") (pintype "passive"))
      (node (ref "K3") (pin "4") (pinfunction "4_4") (pintype "passive"))
      (node (ref "Q1") (pin "2") (pinfunction "SOURCE_2") (pintype "passive"))
      (node (ref "Q15") (pin "2") (pinfunction "SOURCE_2") (pintype "passive"))
      (node (ref "Q2") (pin "2") (pinfunction "SOURCE_2") (pintype "passive"))
      (node (ref "Q3") (pin "2") (pinfunction "SOURCE_2") (pintype "passive"))
      (node (ref "Q4") (pin "2") (pinfunction "SOURCE_2") (pintype "passive"))
      (node (ref "Q5") (pin "2") (pinfunction "SOURCE_2") (pintype "passive"))
      (node (ref "Q9") (pin "2") (pinfunction "SOURCE_2") (pintype "passive"))
      (node (ref "R2603") (pin "2") (pinfunction "2_2") (pintype "passive"))
      (node (ref "R2606") (pin "2") (pinfunction "2_2") (pintype "passive"))
      (node (ref "R2624") (pin "2") (pinfunction "2_2") (pintype "passive"))
      (node (ref "R2625") (pin "2") (pinfunction "2_2") (pintype "passive"))
      (node (ref "R2626") (pin "2") (pinfunction "2_2") (pintype "passive"))
      (node (ref "R2628") (pin "2") (pinfunction "2_2") (pintype "passive"))
      (node (ref "R2946") (pin "2") (pinfunction "2_2") (pintype "passive"))
      (node (ref "TP918") (pin "1") (pinfunction "Pin1_1") (pintype "passive"))
      (node (ref "U702") (pin "10") (pinfunction "AGND_10") (pintype "passive"))
      (node (ref "U702") (pin "2") (pinfunction "PGND_2") (pintype "passive"))
    )
    (net (code "12") (name "L17_GPIO_IO04") (class "Default")
      (node (ref "R2627") (pin "1") (pinfunction "1_1") (pintype "passive"))
    )
    (net (code "13") (name "N20_GPIO_IO12") (class "Default")
      (node (ref "R2629") (pin "1") (pinfunction "1_1") (pintype "passive"))
    )
    (net (code "14") (name "N21_GPIO_IO13") (class "Default")
      (node (ref "R2623") (pin "1") (pinfunction "1_1") (pintype "passive"))
    )
    (net (code "15") (name "Net-(C819-Pad1)") (class "Default")
      (node (ref "C819") (pin "1") (pinfunction "1_1") (pintype "passive"))
      (node (ref "R2597") (pin "2") (pinfunction "2_2") (pintype "passive"))
    )
    (net (code "16") (name "Net-(C822-Pad1)") (class "Default")
      (node (ref "C822") (pin "1") (pinfunction "1_1") (pintype "passive"))
      (node (ref "R2600") (pin "2") (pinfunction "2_2") (pintype "passive"))
      (node (ref "R2602") (pin "1") (pinfunction "1_1") (pintype "passive"))
    )
    (net (code "17") (name "Net-(D603-CATHODE)") (class "Default")
      (node (ref "D603") (pin "C") (pinfunction "CATHODE_C") (pintype "passive"))
      (node (ref "R2598") (pin "1") (pinfunction "1_1") (pintype "passive"))
      (node (ref "R2599") (pin "1") (pinfunction "1_1") (pintype "passive"))
    )
    (net (code "18") (name "Net-(LED1-B)") (class "Default")
      (node (ref "LED1") (pin "2") (pinfunction "B_2") (pintype "passive"))
      (node (ref "R2621") (pin "1") (pinfunction "1_1") (pintype "passive"))
    )
    (net (code "19") (name "Net-(LED1-G)") (class "Default")
      (node (ref "LED1") (pin "3") (pinfunction "G_3") (pintype "passive"))
      (node (ref "R2620") (pin "1") (pinfunction "1_1") (pintype "passive"))
    )
    (net (code "20") (name "Net-(LED1-R)") (class "Default")
      (node (ref "LED1") (pin "4") (pinfunction "R_4") (pintype "passive"))
      (node (ref "R2619") (pin "1") (pinfunction "1_1") (pintype "passive"))
    )
    (net (code "21") (name "Net-(Q1-DRAIN)") (class "Default")
      (node (ref "Q1") (pin "3") (pinfunction "DRAIN_3") (pintype "passive"))
      (node (ref "R2609") (pin "2") (pinfunction "2_2") (pintype "passive"))
    )
    (net (code "22") (name "Net-(Q1-GATE)") (class "Default")
      (node (ref "Q1") (pin "1") (pinfunction "GATE_1") (pintype "input"))
      (node (ref "R2613") (pin "2") (pinfunction "2_2") (pintype "passive"))
      (node (ref "R2614") (pin "2") (pinfunction "2_2") (pintype "passive"))
    )
    (net (code "23") (name "Net-(Q2-DRAIN)") (class "Default")
      (node (ref "Q2") (pin "3") (pinfunction "DRAIN_3") (pintype "passive"))
      (node (ref "R2619") (pin "2") (pinfunction "2_2") (pintype "passive"))
    )
    (net (code "24") (name "Net-(Q3-DRAIN)") (class "Default")
      (node (ref "Q3") (pin "3") (pinfunction "DRAIN_3") (pintype "passive"))
      (node (ref "R2620") (pin "2") (pinfunction "2_2") (pintype "passive"))
    )
    (net (code "25") (name "Net-(Q3-GATE)") (class "Default")
      (node (ref "Q3") (pin "1") (pinfunction "GATE_1") (pintype "input"))
      (node (ref "R2625") (pin "1") (pinfunction "1_1") (pintype "passive"))
      (node (ref "R2627") (pin "2") (pinfunction "2_2") (pintype "passive"))
    )
    (net (code "26") (name "Net-(Q4-DRAIN)") (class "Default")
      (node (ref "Q4") (pin "3") (pinfunction "DRAIN_3") (pintype "passive"))
      (node (ref "R2621") (pin "2") (pinfunction "2_2") (pintype "passive"))
    )
    (net (code "27") (name "Net-(Q4-GATE)") (class "Default")
      (node (ref "Q4") (pin "1") (pinfunction "GATE_1") (pintype "input"))
      (node (ref "R2626") (pin "1") (pinfunction "1_1") (pintype "passive"))
      (node (ref "R2629") (pin "2") (pinfunction "2_2") (pintype "passive"))
    )
    (net (code "28") (name "Net-(Q9-DRAIN)") (class "Default")
      (node (ref "Q9") (pin "3") (pinfunction "DRAIN_3") (pintype "passive"))
      (node (ref "R2605") (pin "1") (pinfunction "1_1") (pintype "passive"))
      (node (ref "R2606") (pin "1") (pinfunction "1_1") (pintype "passive"))
      (node (ref "R2946") (pin "1") (pinfunction "1_1") (pintype "passive"))
      (node (ref "U702") (pin "6") (pinfunction "MODE_6") (pintype "passive"))
    )
    (net (code "29") (name "Net-(Q9-GATE)") (class "Default")
      (node (ref "Q9") (pin "1") (pinfunction "GATE_1") (pintype "input"))
      (node (ref "R3002") (pin "2") (pinfunction "2_2") (pintype "passive"))
    )
    (net (code "30") (name "Net-(Q15-DRAIN)") (class "Default")
      (node (ref "Q15") (pin "3") (pinfunction "DRAIN_3") (pintype "passive"))
      (node (ref "R2943") (pin "2") (pinfunction "2_2") (pintype "passive"))
    )
    (net (code "31") (name "Net-(Q15-GATE)") (class "Default")
      (node (ref "Q15") (pin "1") (pinfunction "GATE_1") (pintype "input"))
      (node (ref "R2945") (pin "2") (pinfunction "2_2") (pintype "passive"))
    )
    (net (code "32") (name "Net-(U702-BST)") (class "Default")
      (node (ref "R2597") (pin "1") (pinfunction "1_1") (pintype "passive"))
      (node (ref "U702") (pin "8") (pinfunction "BST_8") (pintype "passive"))
    )
    (net (code "33") (name "Net-(U702-EN)") (class "Default")
      (node (ref "C832") (pin "1") (pinfunction "1_1") (pintype "passive"))
      (node (ref "R2599") (pin "2") (pinfunction "2_2") (pintype "passive"))
      (node (ref "U702") (pin "12") (pinfunction "EN_12") (pintype "passive"))
    )
    (net (code "34") (name "Net-(U702-FB)") (class "Default")
      (node (ref "R2601") (pin "2") (pinfunction "2_2") (pintype "passive"))
      (node (ref "R2602") (pin "2") (pinfunction "2_2") (pintype "passive"))
      (node (ref "R2603") (pin "1") (pinfunction "1_1") (pintype "passive"))
      (node (ref "U702") (pin "11") (pinfunction "FB_11") (pintype "passive"))
    )
    (net (code "35") (name "Net-(U702-PG)") (class "Default")
      (node (ref "R2604") (pin "2") (pinfunction "2_2") (pintype "passive"))
      (node (ref "U702") (pin "3") (pinfunction "PG_3") (pintype "passive"))
    )
    (net (code "36") (name "Net-(U702-SW)") (class "Default")
      (node (ref "C819") (pin "2") (pinfunction "2_2") (pintype "passive"))
      (node (ref "L707") (pin "1") (pinfunction "1_1") (pintype "passive"))
      (node (ref "R2600") (pin "1") (pinfunction "1_1") (pintype "passive"))
      (node (ref "U702") (pin "7") (pinfunction "SW_7") (pintype "passive"))
    )
    (net (code "37") (name "Net-(U703-G)") (class "Default")
      (node (ref "C1019") (pin "1") (pinfunction "1_1") (pintype "passive"))
      (node (ref "C838") (pin "2") (pinfunction "2_2") (pintype "passive"))
      (node (ref "R2607") (pin "2") (pinfunction "2_2") (pintype "passive"))
      (node (ref "R2609") (pin "1") (pinfunction "1_1") (pintype "passive"))
      (node (ref "U703") (pin "4") (pinfunction "G_4") (pintype "passive"))
    )
    (net (code "38") (name "Net-(U746-C)") (class "Default")
      (node (ref "R2943") (pin "1") (pinfunction "1_1") (pintype "passive"))
      (node (ref "R2947") (pin "2") (pinfunction "2_2") (pintype "passive"))
      (node (ref "R3002") (pin "1") (pinfunction "1_1") (pintype "passive"))
      (node (ref "U746") (pin "2") (pinfunction "C_2") (pintype "passive"))
      (node (ref "U747") (pin "2") (pinfunction "C_2") (pintype "passive"))
    )
    (net (code "39") (name "U20_GPIO_IO23") (class "Default")
      (node (ref "R2611") (pin "2") (pinfunction "2_2") (pintype "passive"))
    )
    (net (code "40") (name "U21_GPIO_IO24") (class "Default")
      (node (ref "R2612") (pin "2") (pinfunction "2_2") (pintype "passive"))
    )
    (net (code "41") (name "VBUS_IN") (class "Default")
      (node (ref "C820") (pin "1") (pinfunction "1_1") (pintype "passive"))
      (node (ref "C821") (pin "1") (pinfunction "1_1") (pintype "passive"))
      (node (ref "C823") (pin "1") (pinfunction "1_1") (pintype "passive"))
      (node (ref "C824") (pin "1") (pinfunction "1_1") (pintype "passive"))
      (node (ref "C825") (pin "1") (pinfunction "1_1") (pintype "passive"))
      (node (ref "R2598") (pin "2") (pinfunction "2_2") (pintype "passive"))
      (node (ref "TP917") (pin "1") (pinfunction "Pin1_1") (pintype "passive"))
      (node (ref "U702") (pin "1") (pinfunction "VIN_1") (pintype "passive"))
    )
    (net (code "42") (name "VCC_3V6") (class "Default")
      (node (ref "C834") (pin "1") (pinfunction "1_1") (pintype "passive"))
      (node (ref "R2604") (pin "1") (pinfunction "1_1") (pintype "passive"))
      (node (ref "R2605") (pin "2") (pinfunction "2_2") (pintype "passive"))
      (node (ref "R2947") (pin "1") (pinfunction "1_1") (pintype "passive"))
      (node (ref "U702") (pin "9") (pinfunction "VCC_9") (pintype "passive"))
    )
    (net (code "43") (name "VDD_3V3") (class "Default")
      (node (ref "R2614") (pin "1") (pinfunction "1_1") (pintype "passive"))
      (node (ref "R2622") (pin "1") (pinfunction "1_1") (pintype "passive"))
    )
    (net (code "44") (name "VDD_5V") (class "Default")
      (node (ref "C1019") (pin "2") (pinfunction "2_2") (pintype "passive"))
      (node (ref "C839") (pin "1") (pinfunction "1_1") (pintype "passive"))
      (node (ref "C840") (pin "1") (pinfunction "1_1") (pintype "passive"))
      (node (ref "LED1") (pin "1") (pinfunction "+_1") (pintype "passive"))
      (node (ref "TP1038") (pin "1") (pinfunction "TP_1") (pintype "passive"))
      (node (ref "U703") (pin "5") (pinfunction "D4_5") (pintype "passive"))
      (node (ref "U703") (pin "6") (pinfunction "D3_6") (pintype "passive"))
      (node (ref "U703") (pin "7") (pinfunction "D2_7") (pintype "passive"))
      (node (ref "U703") (pin "8") (pinfunction "D1_8") (pintype "passive"))
    )
    (net (code "45") (name "VSYS_5V") (class "Default")
      (node (ref "C822") (pin "2") (pinfunction "2_2") (pintype "passive"))
      (node (ref "C827") (pin "1") (pinfunction "1_1") (pintype "passive"))
      (node (ref "C828") (pin "1") (pinfunction "1_1") (pintype "passive"))
      (node (ref "C829") (pin "1") (pinfunction "1_1") (pintype "passive"))
      (node (ref "C830") (pin "1") (pinfunction "1_1") (pintype "passive"))
      (node (ref "C831") (pin "1") (pinfunction "1_1") (pintype "passive"))
      (node (ref "C833") (pin "1") (pinfunction "1_1") (pintype "passive"))
      (node (ref "C837") (pin "1") (pinfunction "1_1") (pintype "passive"))
      (node (ref "C838") (pin "1") (pinfunction "1_1") (pintype "passive"))
      (node (ref "L707") (pin "2") (pinfunction "2_2") (pintype "passive"))
      (node (ref "R2601") (pin "1") (pinfunction "1_1") (pintype "passive"))
      (node (ref "R2607") (pin "1") (pinfunction "1_1") (pintype "passive"))
      (node (ref "TP1023") (pin "1") (pinfunction "TP_1") (pintype "passive"))
      (node (ref "TP1037") (pin "1") (pinfunction "TP_1") (pintype "passive"))
      (node (ref "U702") (pin "5") (pinfunction "VOUT_5") (pintype "passive"))
      (node (ref "U703") (pin "1") (pinfunction "S1_1") (pintype "passive"))
      (node (ref "U703") (pin "2") (pinfunction "S2_2") (pintype "passive"))
      (node (ref "U703") (pin "3") (pinfunction "S3_3") (pintype "passive"))
    )
    (net (code "46") (name "unconnected-(U702-NC-Pad4)") (class "Default")
      (node (ref "U702") (pin "4") (pinfunction "NC_4") (pintype "passive+no_connect"))
    )
  )
)
